# TouScruino-arm-ui2-v0.net
KiCad netlist of a schematic drawn in EAGLE
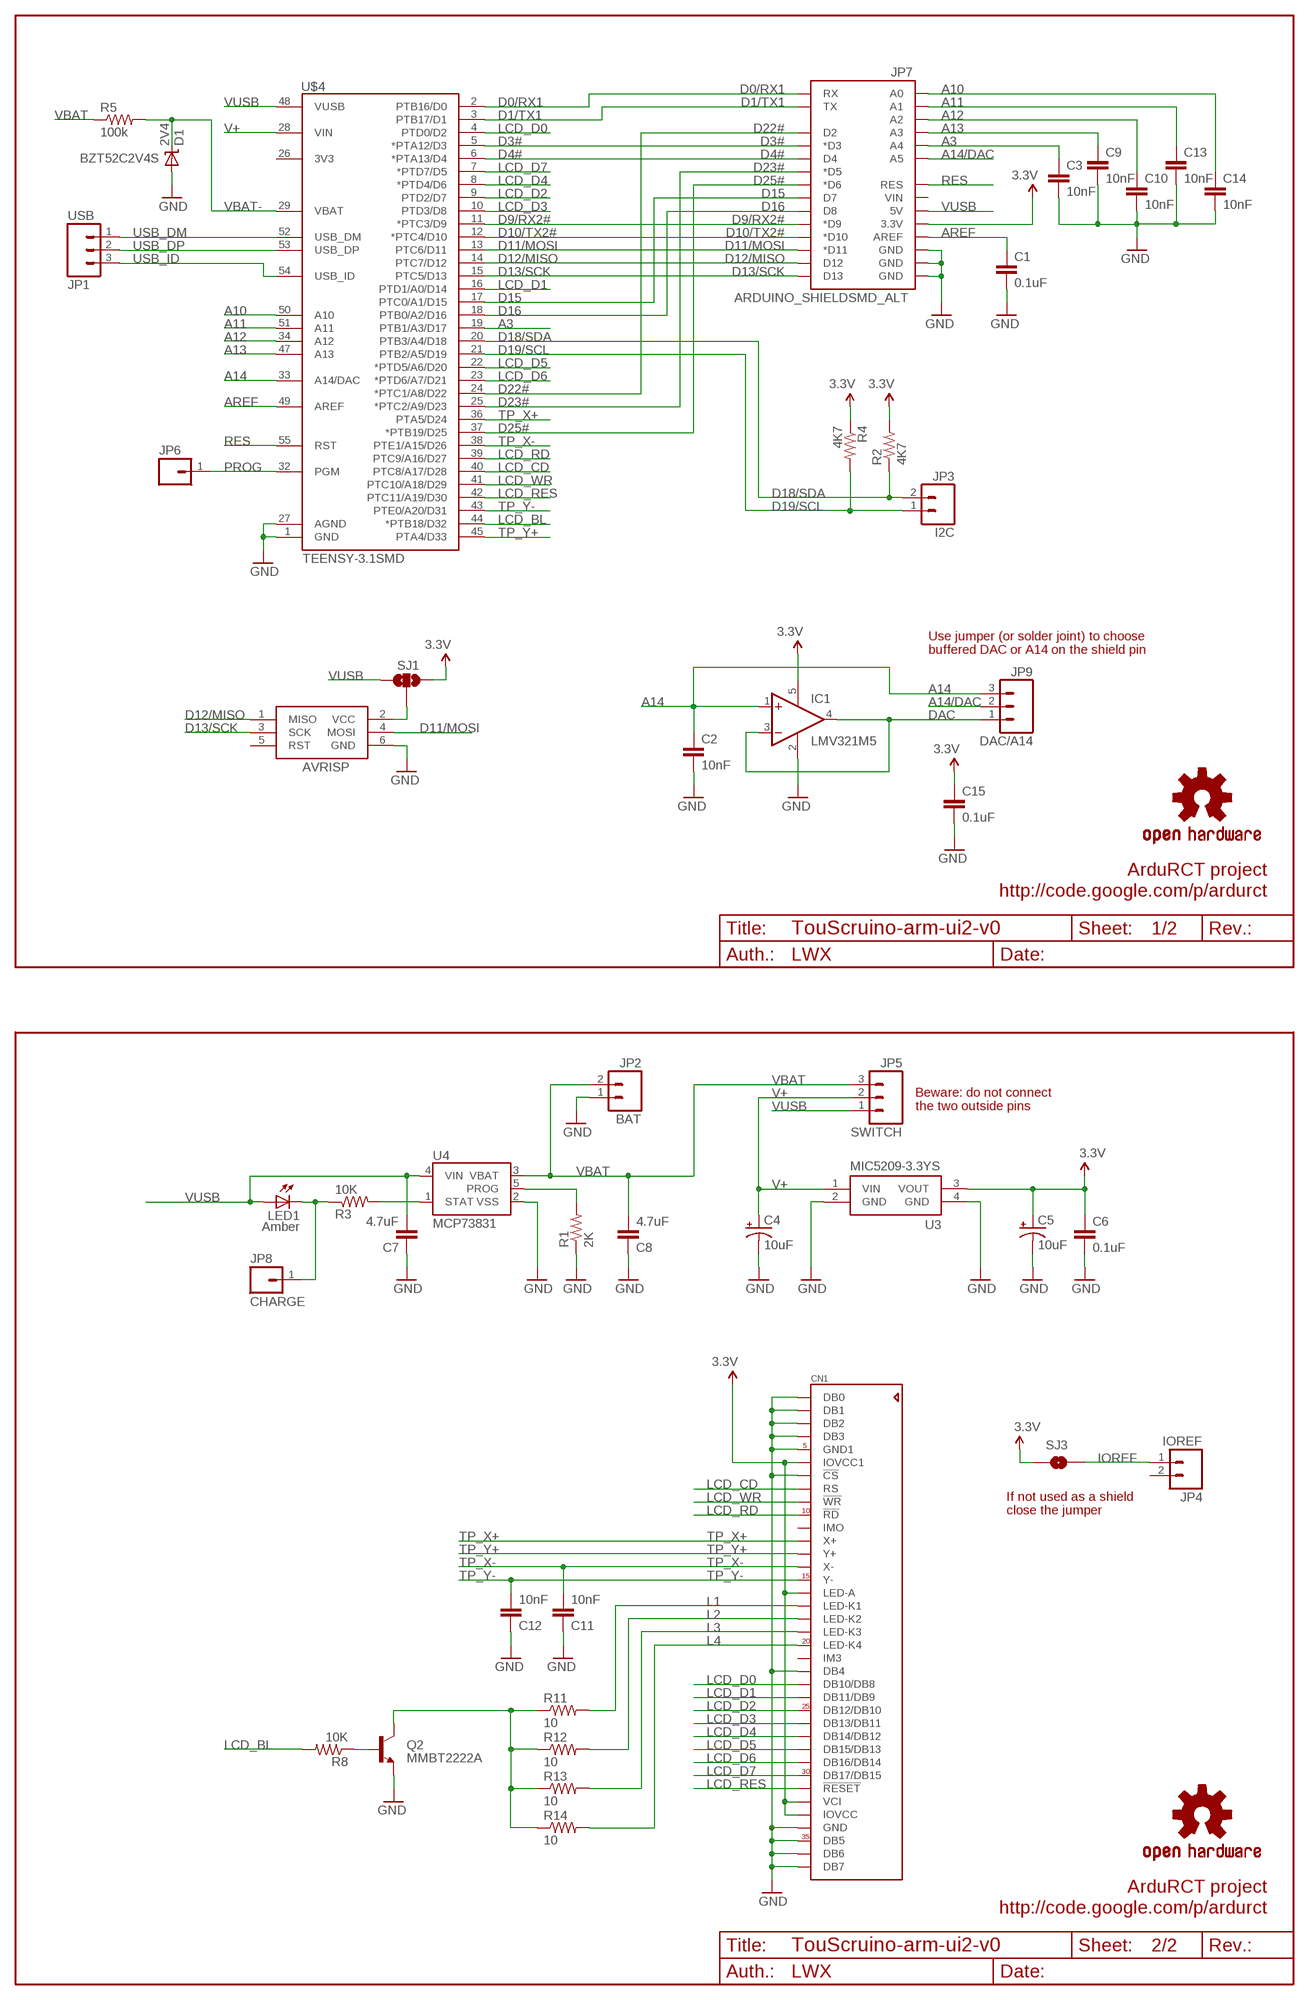
[diagram p0: schematic, sheet 1]

(export (version "E")
  (design (tool "Eeschema 10.0.6"))
  (components
    (comp (ref "AVRISP")
      (value "AVRISP")
      (footprint "eagle-import:2X3_SMD")
      (libsource (lib "eagle-import") (part "AVRISP"))
    )
    (comp (ref "C1")
      (value "0.1uF")
      (footprint "eagle-import:0805")
      (libsource (lib "eagle-import") (part "CAP0805"))
    )
    (comp (ref "C2")
      (value "10nF")
      (footprint "eagle-import:0805")
      (libsource (lib "eagle-import") (part "CAP0805"))
    )
    (comp (ref "C3")
      (value "10nF")
      (footprint "eagle-import:0805")
      (libsource (lib "eagle-import") (part "CAP0805"))
    )
    (comp (ref "C4")
      (value "10uF")
      (footprint "eagle-import:EIA3216")
      (libsource (lib "eagle-import") (part "CAP_POL1206"))
    )
    (comp (ref "C5")
      (value "10uF")
      (footprint "eagle-import:EIA3216")
      (libsource (lib "eagle-import") (part "CAP_POL1206"))
    )
    (comp (ref "C6")
      (value "0.1uF")
      (footprint "eagle-import:0805")
      (libsource (lib "eagle-import") (part "CAP0805"))
    )
    (comp (ref "C7")
      (value "4.7uF")
      (footprint "eagle-import:0805")
      (libsource (lib "eagle-import") (part "CAP0805"))
    )
    (comp (ref "C8")
      (value "4.7uF")
      (footprint "eagle-import:0805")
      (libsource (lib "eagle-import") (part "CAP0805"))
    )
    (comp (ref "C9")
      (value "10nF")
      (footprint "eagle-import:0805")
      (libsource (lib "eagle-import") (part "CAP0805"))
    )
    (comp (ref "C10")
      (value "10nF")
      (footprint "eagle-import:0805")
      (libsource (lib "eagle-import") (part "CAP0805"))
    )
    (comp (ref "C11")
      (value "10nF")
      (footprint "eagle-import:0805")
      (libsource (lib "eagle-import") (part "CAP0805"))
    )
    (comp (ref "C12")
      (value "10nF")
      (footprint "eagle-import:0805")
      (libsource (lib "eagle-import") (part "CAP0805"))
    )
    (comp (ref "C13")
      (value "10nF")
      (footprint "eagle-import:0805")
      (libsource (lib "eagle-import") (part "CAP0805"))
    )
    (comp (ref "C14")
      (value "10nF")
      (footprint "eagle-import:0805")
      (libsource (lib "eagle-import") (part "CAP0805"))
    )
    (comp (ref "C15")
      (value "0.1uF")
      (footprint "eagle-import:0805")
      (libsource (lib "eagle-import") (part "CAP0805"))
    )
    (comp (ref "CN1")
      (value "ILI9325_LCD1.0MM")
      (footprint "eagle-import:ILI9325_28INCH_TS")
      (libsource (lib "eagle-import") (part "ILI9325_LCD1.0MM"))
    )
    (comp (ref "D1")
      (value "2V4")
      (footprint "eagle-import:SOD-323")
      (libsource (lib "eagle-import") (part "DIODE-ZENER-BZT52"))
    )
    (comp (ref "IC1")
      (value "LMV321M5")
      (footprint "eagle-import:SOT23-5")
      (libsource (lib "eagle-import") (part "LMV321?M5"))
    )
    (comp (ref "JP1")
      (value "USB")
      (footprint "eagle-import:1X03_SMD_ALT")
      (libsource (lib "eagle-import") (part "M03SMD"))
    )
    (comp (ref "JP2")
      (value "BAT")
      (footprint "eagle-import:JST-2-SMD")
      (libsource (lib "eagle-import") (part "M02-JST-2MM-SMT"))
    )
    (comp (ref "JP3")
      (value "I2C")
      (footprint "eagle-import:1X02_SMD_ALT")
      (libsource (lib "eagle-import") (part "M02SMD_ALT"))
    )
    (comp (ref "JP4")
      (value "IOREF")
      (footprint "eagle-import:1X02_SMD_ALT")
      (libsource (lib "eagle-import") (part "M02SMD_ALT"))
    )
    (comp (ref "JP5")
      (value "SWITCH")
      (footprint "eagle-import:1X03_SMD_TH")
      (libsource (lib "eagle-import") (part "M03SMD_TH"))
    )
    (comp (ref "JP6")
      (value "M01SMD_TH")
      (footprint "eagle-import:1X01_SMD_TH")
      (libsource (lib "eagle-import") (part "M01SMD_TH"))
    )
    (comp (ref "JP7")
      (value "ARDUINO_SHIELDSMD_ALT")
      (footprint "eagle-import:ARDUINO_SHIELD_SMD_ALT")
      (libsource (lib "eagle-import") (part "ARDUINO_SHIELDSMD_ALT"))
    )
    (comp (ref "JP8")
      (value "CHARGE")
      (footprint "eagle-import:1X01_SMD")
      (libsource (lib "eagle-import") (part "M01SMD"))
    )
    (comp (ref "JP9")
      (value "DAC/A14")
      (footprint "eagle-import:1X03_SMD_SJ")
      (libsource (lib "eagle-import") (part "M03SMD_SJ"))
    )
    (comp (ref "LED1")
      (value "Amber")
      (footprint "eagle-import:LED")
      (libsource (lib "eagle-import") (part "LED"))
    )
    (comp (ref "Q2")
      (value "MMBT2222A")
      (footprint "eagle-import:SOT23-3")
      (libsource (lib "eagle-import") (part "TRANSISTOR_NPNSOT23-3"))
    )
    (comp (ref "R1")
      (value "2K")
      (footprint "eagle-import:0805")
      (libsource (lib "eagle-import") (part "RESISTOR0805-RES"))
    )
    (comp (ref "R2")
      (value "4K7")
      (footprint "eagle-import:0805")
      (libsource (lib "eagle-import") (part "RESISTOR0805-RES"))
    )
    (comp (ref "R3")
      (value "10K")
      (footprint "eagle-import:0805")
      (libsource (lib "eagle-import") (part "RESISTOR0805-RES"))
    )
    (comp (ref "R4")
      (value "4K7")
      (footprint "eagle-import:0805")
      (libsource (lib "eagle-import") (part "RESISTOR0805-RES"))
    )
    (comp (ref "R5")
      (value "100k")
      (footprint "eagle-import:0805")
      (libsource (lib "eagle-import") (part "RESISTOR0805-RES"))
    )
    (comp (ref "R8")
      (value "10K")
      (footprint "eagle-import:0805")
      (libsource (lib "eagle-import") (part "RESISTOR0805-RES"))
    )
    (comp (ref "R11")
      (value "10")
      (footprint "eagle-import:0805")
      (libsource (lib "eagle-import") (part "RESISTOR0805-RES"))
    )
    (comp (ref "R12")
      (value "10")
      (footprint "eagle-import:0805")
      (libsource (lib "eagle-import") (part "RESISTOR0805-RES"))
    )
    (comp (ref "R13")
      (value "10")
      (footprint "eagle-import:0805")
      (libsource (lib "eagle-import") (part "RESISTOR0805-RES"))
    )
    (comp (ref "R14")
      (value "10")
      (footprint "eagle-import:0805")
      (libsource (lib "eagle-import") (part "RESISTOR0805-RES"))
    )
    (comp (ref "SJ1")
      (value "SJ_2WAYS")
      (footprint "eagle-import:SJ_2WAYS")
      (libsource (lib "eagle-import") (part "SJ_2WAYS"))
    )
    (comp (ref "SJ3")
      (value "SOLDERJUMPERNO")
      (footprint "eagle-import:SJ_2S-NO")
      (libsource (lib "eagle-import") (part "SOLDERJUMPERNO"))
    )
    (comp (ref "U$3")
      (value "OSHW-LOGOM")
      (footprint "eagle-import:OSHW-LOGO-M")
      (libsource (lib "eagle-import") (part "OSHW-LOGOM"))
    )
    (comp (ref "U$4")
      (value "TEENSY-3.1SMD")
      (footprint "eagle-import:TEENSY-3.1_HSMD")
      (libsource (lib "eagle-import") (part "TEENSY-3.1SMD"))
    )
    (comp (ref "U$5")
      (value "OSHW-LOGOM")
      (footprint "eagle-import:OSHW-LOGO-M")
      (libsource (lib "eagle-import") (part "OSHW-LOGOM"))
    )
    (comp (ref "U3")
      (value "MIC5209-3.3YS")
      (footprint "eagle-import:SOT223")
      (libsource (lib "eagle-import") (part "MIC5209"))
    )
    (comp (ref "U4")
      (value "MCP73831")
      (footprint "eagle-import:SOT23-5")
      (libsource (lib "eagle-import") (part "MCP73831"))
    )
  )
  (nets
    (net (code "1") (name "/A3") (class "Default")
      (node (ref "C3") (pin "1") (pinfunction "1_1") (pintype "passive"))
      (node (ref "JP7") (pin "A4") (pinfunction "A4_A4") (pintype "bidirectional"))
      (node (ref "U$4") (pin "19") (pinfunction "PTB1/A3/D17_19") (pintype "bidirectional"))
    )
    (net (code "2") (name "/A10") (class "Default")
      (node (ref "C14") (pin "1") (pinfunction "1_1") (pintype "passive"))
      (node (ref "JP7") (pin "A0") (pinfunction "A0_A0") (pintype "bidirectional"))
      (node (ref "U$4") (pin "50") (pinfunction "A10_50") (pintype "bidirectional"))
    )
    (net (code "3") (name "/A11") (class "Default")
      (node (ref "C13") (pin "1") (pinfunction "1_1") (pintype "passive"))
      (node (ref "JP7") (pin "A1") (pinfunction "A1_A1") (pintype "bidirectional"))
      (node (ref "U$4") (pin "51") (pinfunction "A11_51") (pintype "bidirectional"))
    )
    (net (code "4") (name "/A12") (class "Default")
      (node (ref "C10") (pin "1") (pinfunction "1_1") (pintype "passive"))
      (node (ref "JP7") (pin "A2") (pinfunction "A2_A2") (pintype "bidirectional"))
      (node (ref "U$4") (pin "34") (pinfunction "A12_34") (pintype "bidirectional"))
    )
    (net (code "5") (name "/A13") (class "Default")
      (node (ref "C9") (pin "1") (pinfunction "1_1") (pintype "passive"))
      (node (ref "JP7") (pin "A3") (pinfunction "A3_A3") (pintype "bidirectional"))
      (node (ref "U$4") (pin "47") (pinfunction "A13_47") (pintype "bidirectional"))
    )
    (net (code "6") (name "/A14") (class "Default")
      (node (ref "C2") (pin "1") (pinfunction "1_1") (pintype "passive"))
      (node (ref "IC1") (pin "1") (pinfunction "+IN_1") (pintype "input"))
      (node (ref "JP9") (pin "3") (pinfunction "3_3") (pintype "passive"))
      (node (ref "U$4") (pin "33") (pinfunction "A14/DAC_33") (pintype "bidirectional"))
    )
    (net (code "7") (name "/A14{slash}DAC") (class "Default")
      (node (ref "JP7") (pin "A5") (pinfunction "A5_A5") (pintype "bidirectional"))
      (node (ref "JP9") (pin "2") (pinfunction "2_2") (pintype "passive"))
    )
    (net (code "8") (name "/AREF") (class "Default")
      (node (ref "C1") (pin "1") (pinfunction "1_1") (pintype "passive"))
      (node (ref "JP7") (pin "AREF") (pinfunction "AREF_AREF") (pintype "bidirectional"))
      (node (ref "U$4") (pin "49") (pinfunction "AREF_49") (pintype "bidirectional"))
    )
    (net (code "9") (name "/D0{slash}RX1") (class "Default")
      (node (ref "JP7") (pin "RX") (pinfunction "RX_RX") (pintype "bidirectional"))
      (node (ref "U$4") (pin "2") (pinfunction "PTB16/D0_2") (pintype "bidirectional"))
    )
    (net (code "10") (name "/D1{slash}TX1") (class "Default")
      (node (ref "JP7") (pin "TX") (pinfunction "TX_TX") (pintype "bidirectional"))
      (node (ref "U$4") (pin "3") (pinfunction "PTB17/D1_3") (pintype "bidirectional"))
    )
    (net (code "11") (name "/D3#") (class "Default")
      (node (ref "JP7") (pin "D3") (pinfunction "*D3_D3") (pintype "bidirectional"))
      (node (ref "U$4") (pin "5") (pinfunction "*PTA12/D3_5") (pintype "bidirectional"))
    )
    (net (code "12") (name "/D4#") (class "Default")
      (node (ref "JP7") (pin "D4") (pinfunction "D4_D4") (pintype "bidirectional"))
      (node (ref "U$4") (pin "6") (pinfunction "*PTA13/D4_6") (pintype "bidirectional"))
    )
    (net (code "13") (name "/D9{slash}RX2#") (class "Default")
      (node (ref "JP7") (pin "D9") (pinfunction "*D9_D9") (pintype "bidirectional"))
      (node (ref "U$4") (pin "11") (pinfunction "*PTC3/D9_11") (pintype "bidirectional"))
    )
    (net (code "14") (name "/D10{slash}TX2#") (class "Default")
      (node (ref "JP7") (pin "D10") (pinfunction "*D10_D10") (pintype "bidirectional"))
      (node (ref "U$4") (pin "12") (pinfunction "*PTC4/D10_12") (pintype "bidirectional"))
    )
    (net (code "15") (name "/D11{slash}MOSI") (class "Default")
      (node (ref "AVRISP") (pin "4") (pinfunction "MOSI_4") (pintype "output"))
      (node (ref "JP7") (pin "D11") (pinfunction "*D11_D11") (pintype "bidirectional"))
      (node (ref "U$4") (pin "13") (pinfunction "PTC6/D11_13") (pintype "bidirectional"))
    )
    (net (code "16") (name "/D12{slash}MISO") (class "Default")
      (node (ref "AVRISP") (pin "1") (pinfunction "MISO_1") (pintype "input"))
      (node (ref "JP7") (pin "D12") (pinfunction "D12_D12") (pintype "bidirectional"))
      (node (ref "U$4") (pin "14") (pinfunction "PTC7/D12_14") (pintype "bidirectional"))
    )
    (net (code "17") (name "/D13{slash}SCK") (class "Default")
      (node (ref "AVRISP") (pin "3") (pinfunction "SCK_3") (pintype "output"))
      (node (ref "JP7") (pin "D13") (pinfunction "D13_D13") (pintype "bidirectional"))
      (node (ref "U$4") (pin "15") (pinfunction "PTC5/D13_15") (pintype "bidirectional"))
    )
    (net (code "18") (name "/D15") (class "Default")
      (node (ref "JP7") (pin "D7") (pinfunction "D7_D7") (pintype "bidirectional"))
      (node (ref "U$4") (pin "17") (pinfunction "PTC0/A1/D15_17") (pintype "bidirectional"))
    )
    (net (code "19") (name "/D16") (class "Default")
      (node (ref "JP7") (pin "D8") (pinfunction "D8_D8") (pintype "bidirectional"))
      (node (ref "U$4") (pin "18") (pinfunction "PTB0/A2/D16_18") (pintype "bidirectional"))
    )
    (net (code "20") (name "/D18{slash}SDA") (class "Default")
      (node (ref "JP3") (pin "2") (pinfunction "2_2") (pintype "passive"))
      (node (ref "R2") (pin "1") (pinfunction "1_1") (pintype "passive"))
      (node (ref "U$4") (pin "20") (pinfunction "PTB3/A4/D18_20") (pintype "bidirectional"))
    )
    (net (code "21") (name "/D19{slash}SCL") (class "Default")
      (node (ref "JP3") (pin "1") (pinfunction "1_1") (pintype "passive"))
      (node (ref "R4") (pin "2") (pinfunction "2_2") (pintype "passive"))
      (node (ref "U$4") (pin "21") (pinfunction "PTB2/A5/D19_21") (pintype "bidirectional"))
    )
    (net (code "22") (name "/D22#") (class "Default")
      (node (ref "JP7") (pin "D2") (pinfunction "D2_D2") (pintype "bidirectional"))
      (node (ref "U$4") (pin "24") (pinfunction "*PTC1/A8/D22_24") (pintype "bidirectional"))
    )
    (net (code "23") (name "/D23#") (class "Default")
      (node (ref "JP7") (pin "D5") (pinfunction "*D5_D5") (pintype "bidirectional"))
      (node (ref "U$4") (pin "25") (pinfunction "*PTC2/A9/D23_25") (pintype "bidirectional"))
    )
    (net (code "24") (name "/D25#") (class "Default")
      (node (ref "JP7") (pin "D6") (pinfunction "*D6_D6") (pintype "bidirectional"))
      (node (ref "U$4") (pin "37") (pinfunction "*PTB19/D25_37") (pintype "bidirectional"))
    )
    (net (code "25") (name "/DAC") (class "Default")
      (node (ref "IC1") (pin "3") (pinfunction "-IN_3") (pintype "input"))
      (node (ref "IC1") (pin "4") (pinfunction "OUT_4") (pintype "output"))
      (node (ref "JP9") (pin "1") (pinfunction "1_1") (pintype "passive"))
    )
    (net (code "26") (name "/IOREF") (class "Default")
      (node (ref "JP4") (pin "1") (pinfunction "1_1") (pintype "passive"))
      (node (ref "SJ3") (pin "2") (pinfunction "2_2") (pintype "passive"))
    )
    (net (code "27") (name "/L1") (class "Default")
      (node (ref "CN1") (pin "17") (pinfunction "LED-K1_17") (pintype "passive"))
      (node (ref "R11") (pin "2") (pinfunction "2_2") (pintype "passive"))
    )
    (net (code "28") (name "/L2") (class "Default")
      (node (ref "CN1") (pin "18") (pinfunction "LED-K2_18") (pintype "passive"))
      (node (ref "R12") (pin "2") (pinfunction "2_2") (pintype "passive"))
    )
    (net (code "29") (name "/L3") (class "Default")
      (node (ref "CN1") (pin "19") (pinfunction "LED-K3_19") (pintype "passive"))
      (node (ref "R13") (pin "2") (pinfunction "2_2") (pintype "passive"))
    )
    (net (code "30") (name "/L4") (class "Default")
      (node (ref "CN1") (pin "20") (pinfunction "LED-K4_20") (pintype "passive"))
      (node (ref "R14") (pin "2") (pinfunction "2_2") (pintype "passive"))
    )
    (net (code "31") (name "/LCD_BL") (class "Default")
      (node (ref "R8") (pin "2") (pinfunction "2_2") (pintype "passive"))
      (node (ref "U$4") (pin "44") (pinfunction "*PTB18/D32_44") (pintype "bidirectional"))
    )
    (net (code "32") (name "/LCD_CD") (class "Default")
      (node (ref "CN1") (pin "8") (pinfunction "RS_8") (pintype "passive"))
      (node (ref "U$4") (pin "40") (pinfunction "PTC8/A17/D28_40") (pintype "bidirectional"))
    )
    (net (code "33") (name "/LCD_D0") (class "Default")
      (node (ref "CN1") (pin "23") (pinfunction "DB10/DB8_23") (pintype "passive"))
      (node (ref "U$4") (pin "4") (pinfunction "PTD0/D2_4") (pintype "bidirectional"))
    )
    (net (code "34") (name "/LCD_D1") (class "Default")
      (node (ref "CN1") (pin "24") (pinfunction "DB11/DB9_24") (pintype "passive"))
      (node (ref "U$4") (pin "16") (pinfunction "PTD1/A0/D14_16") (pintype "bidirectional"))
    )
    (net (code "35") (name "/LCD_D2") (class "Default")
      (node (ref "CN1") (pin "25") (pinfunction "DB12/DB10_25") (pintype "passive"))
      (node (ref "U$4") (pin "9") (pinfunction "PTD2/D7_9") (pintype "bidirectional"))
    )
    (net (code "36") (name "/LCD_D3") (class "Default")
      (node (ref "CN1") (pin "26") (pinfunction "DB13/DB11_26") (pintype "passive"))
      (node (ref "U$4") (pin "10") (pinfunction "PTD3/D8_10") (pintype "bidirectional"))
    )
    (net (code "37") (name "/LCD_D4") (class "Default")
      (node (ref "CN1") (pin "27") (pinfunction "DB14/DB12_27") (pintype "passive"))
      (node (ref "U$4") (pin "8") (pinfunction "*PTD4/D6_8") (pintype "bidirectional"))
    )
    (net (code "38") (name "/LCD_D5") (class "Default")
      (node (ref "CN1") (pin "28") (pinfunction "DB15/DB13_28") (pintype "passive"))
      (node (ref "U$4") (pin "22") (pinfunction "*PTD5/A6/D20_22") (pintype "bidirectional"))
    )
    (net (code "39") (name "/LCD_D6") (class "Default")
      (node (ref "CN1") (pin "29") (pinfunction "DB16/DB14_29") (pintype "passive"))
      (node (ref "U$4") (pin "23") (pinfunction "*PTD6/A7/D21_23") (pintype "bidirectional"))
    )
    (net (code "40") (name "/LCD_D7") (class "Default")
      (node (ref "CN1") (pin "30") (pinfunction "DB17/DB15_30") (pintype "passive"))
      (node (ref "U$4") (pin "7") (pinfunction "*PTD7/D5_7") (pintype "bidirectional"))
    )
    (net (code "41") (name "/LCD_RD") (class "Default")
      (node (ref "CN1") (pin "10") (pinfunction "~{RD}_10") (pintype "passive"))
      (node (ref "U$4") (pin "39") (pinfunction "PTC9/A16/D27_39") (pintype "bidirectional"))
    )
    (net (code "42") (name "/LCD_RES") (class "Default")
      (node (ref "CN1") (pin "31") (pinfunction "~{RESET}_31") (pintype "passive"))
      (node (ref "U$4") (pin "42") (pinfunction "PTC11/A19/D30_42") (pintype "bidirectional"))
    )
    (net (code "43") (name "/LCD_WR") (class "Default")
      (node (ref "CN1") (pin "9") (pinfunction "~{WR}_9") (pintype "passive"))
      (node (ref "U$4") (pin "41") (pinfunction "PTC10/A18/D29_41") (pintype "bidirectional"))
    )
    (net (code "44") (name "/PROG") (class "Default")
      (node (ref "JP6") (pin "1") (pinfunction "1_1") (pintype "passive"))
      (node (ref "U$4") (pin "32") (pinfunction "PGM_32") (pintype "bidirectional"))
    )
    (net (code "45") (name "/RES") (class "Default")
      (node (ref "JP7") (pin "RES") (pinfunction "RES_RES") (pintype "bidirectional"))
      (node (ref "U$4") (pin "55") (pinfunction "RST_55") (pintype "bidirectional"))
    )
    (net (code "46") (name "/TP_X+") (class "Default")
      (node (ref "CN1") (pin "12") (pinfunction "X+_12") (pintype "passive"))
      (node (ref "U$4") (pin "36") (pinfunction "PTA5/D24_36") (pintype "bidirectional"))
    )
    (net (code "47") (name "/TP_X-") (class "Default")
      (node (ref "C11") (pin "2") (pinfunction "2_2") (pintype "passive"))
      (node (ref "CN1") (pin "14") (pinfunction "X-_14") (pintype "passive"))
      (node (ref "U$4") (pin "38") (pinfunction "PTE1/A15/D26_38") (pintype "bidirectional"))
    )
    (net (code "48") (name "/TP_Y+") (class "Default")
      (node (ref "CN1") (pin "13") (pinfunction "Y+_13") (pintype "passive"))
      (node (ref "U$4") (pin "45") (pinfunction "PTA4/D33_45") (pintype "bidirectional"))
    )
    (net (code "49") (name "/TP_Y-") (class "Default")
      (node (ref "C12") (pin "2") (pinfunction "2_2") (pintype "passive"))
      (node (ref "CN1") (pin "15") (pinfunction "Y-_15") (pintype "passive"))
      (node (ref "U$4") (pin "43") (pinfunction "PTE0/A20/D31_43") (pintype "bidirectional"))
    )
    (net (code "50") (name "/USB_DM") (class "Default")
      (node (ref "JP1") (pin "1") (pinfunction "1_1") (pintype "passive"))
      (node (ref "U$4") (pin "52") (pinfunction "USB_DM_52") (pintype "bidirectional"))
    )
    (net (code "51") (name "/USB_DP") (class "Default")
      (node (ref "JP1") (pin "2") (pinfunction "2_2") (pintype "passive"))
      (node (ref "U$4") (pin "53") (pinfunction "USB_DP_53") (pintype "bidirectional"))
    )
    (net (code "52") (name "/USB_ID") (class "Default")
      (node (ref "JP1") (pin "3") (pinfunction "3_3") (pintype "passive"))
      (node (ref "U$4") (pin "54") (pinfunction "USB_ID_54") (pintype "bidirectional"))
    )
    (net (code "53") (name "/V+") (class "Default")
      (node (ref "C4") (pin "A") (pinfunction "+_A") (pintype "passive"))
      (node (ref "JP5") (pin "2") (pinfunction "2_2") (pintype "passive"))
      (node (ref "U$4") (pin "28") (pinfunction "VIN_28") (pintype "bidirectional"))
      (node (ref "U3") (pin "1") (pinfunction "VIN_1") (pintype "bidirectional"))
    )
    (net (code "54") (name "/VBAT") (class "Default")
      (node (ref "C8") (pin "2") (pinfunction "2_2") (pintype "passive"))
      (node (ref "JP2") (pin "2") (pinfunction "2_2") (pintype "passive"))
      (node (ref "JP5") (pin "3") (pinfunction "3_3") (pintype "passive"))
      (node (ref "R5") (pin "1") (pinfunction "1_1") (pintype "passive"))
      (node (ref "U4") (pin "3") (pinfunction "VBAT_3") (pintype "power_in"))
    )
    (net (code "55") (name "/VBAT-") (class "Default")
      (node (ref "D1") (pin "1") (pinfunction "C_1") (pintype "passive"))
      (node (ref "R5") (pin "2") (pinfunction "2_2") (pintype "passive"))
      (node (ref "U$4") (pin "29") (pinfunction "VBAT_29") (pintype "bidirectional"))
    )
    (net (code "56") (name "/VUSB") (class "Default")
      (node (ref "C7") (pin "2") (pinfunction "2_2") (pintype "passive"))
      (node (ref "JP5") (pin "1") (pinfunction "1_1") (pintype "passive"))
      (node (ref "JP7") (pin "5V") (pinfunction "5V_5V") (pintype "bidirectional"))
      (node (ref "LED1") (pin "A1") (pinfunction "A_A1") (pintype "passive"))
      (node (ref "SJ1") (pin "1") (pinfunction "1_1") (pintype "passive"))
      (node (ref "U$4") (pin "48") (pinfunction "VUSB_48") (pintype "bidirectional"))
      (node (ref "U4") (pin "4") (pinfunction "VIN_4") (pintype "power_in"))
    )
    (net (code "57") (name "3.3V") (class "Default")
      (node (ref "C15") (pin "1") (pinfunction "1_1") (pintype "passive"))
      (node (ref "C5") (pin "A") (pinfunction "+_A") (pintype "passive"))
      (node (ref "C6") (pin "1") (pinfunction "1_1") (pintype "passive"))
      (node (ref "CN1") (pin "16") (pinfunction "LED-A_16") (pintype "passive"))
      (node (ref "CN1") (pin "32") (pinfunction "VCI_32") (pintype "power_in"))
      (node (ref "CN1") (pin "33") (pinfunction "IOVCC_33") (pintype "power_in"))
      (node (ref "CN1") (pin "6") (pinfunction "IOVCC1_6") (pintype "power_in"))
      (node (ref "IC1") (pin "5") (pinfunction "V+_5") (pintype "power_in"))
      (node (ref "JP7") (pin "3.3V") (pinfunction "3.3V_3.3V") (pintype "bidirectional"))
      (node (ref "R2") (pin "2") (pinfunction "2_2") (pintype "passive"))
      (node (ref "R4") (pin "1") (pinfunction "1_1") (pintype "passive"))
      (node (ref "SJ1") (pin "3") (pinfunction "3_3") (pintype "passive"))
      (node (ref "SJ3") (pin "1") (pinfunction "1_1") (pintype "passive"))
      (node (ref "U3") (pin "3") (pinfunction "VOUT_3") (pintype "bidirectional"))
    )
    (net (code "58") (name "GND") (class "Default")
      (node (ref "AVRISP") (pin "6") (pinfunction "GND_6") (pintype "power_in"))
      (node (ref "C1") (pin "2") (pinfunction "2_2") (pintype "passive"))
      (node (ref "C10") (pin "2") (pinfunction "2_2") (pintype "passive"))
      (node (ref "C11") (pin "1") (pinfunction "1_1") (pintype "passive"))
      (node (ref "C12") (pin "1") (pinfunction "1_1") (pintype "passive"))
      (node (ref "C13") (pin "2") (pinfunction "2_2") (pintype "passive"))
      (node (ref "C14") (pin "2") (pinfunction "2_2") (pintype "passive"))
      (node (ref "C15") (pin "2") (pinfunction "2_2") (pintype "passive"))
      (node (ref "C2") (pin "2") (pinfunction "2_2") (pintype "passive"))
      (node (ref "C3") (pin "2") (pinfunction "2_2") (pintype "passive"))
      (node (ref "C4") (pin "C") (pinfunction "-_C") (pintype "passive"))
      (node (ref "C5") (pin "C") (pinfunction "-_C") (pintype "passive"))
      (node (ref "C6") (pin "2") (pinfunction "2_2") (pintype "passive"))
      (node (ref "C7") (pin "1") (pinfunction "1_1") (pintype "passive"))
      (node (ref "C8") (pin "1") (pinfunction "1_1") (pintype "passive"))
      (node (ref "C9") (pin "2") (pinfunction "2_2") (pintype "passive"))
      (node (ref "CN1") (pin "1") (pinfunction "DB0_1") (pintype "passive"))
      (node (ref "CN1") (pin "2") (pinfunction "DB1_2") (pintype "passive"))
      (node (ref "CN1") (pin "22") (pinfunction "DB4_22") (pintype "passive"))
      (node (ref "CN1") (pin "3") (pinfunction "DB2_3") (pintype "passive"))
      (node (ref "CN1") (pin "34") (pinfunction "GND_34") (pintype "power_in"))
      (node (ref "CN1") (pin "35") (pinfunction "DB5_35") (pintype "passive"))
      (node (ref "CN1") (pin "36") (pinfunction "DB6_36") (pintype "passive"))
      (node (ref "CN1") (pin "37") (pinfunction "DB7_37") (pintype "passive"))
      (node (ref "CN1") (pin "4") (pinfunction "DB3_4") (pintype "passive"))
      (node (ref "CN1") (pin "5") (pinfunction "GND1_5") (pintype "power_in"))
      (node (ref "CN1") (pin "7") (pinfunction "~{CS}_7") (pintype "passive"))
      (node (ref "D1") (pin "2") (pinfunction "A_2") (pintype "passive"))
      (node (ref "IC1") (pin "2") (pinfunction "V-_2") (pintype "power_in"))
      (node (ref "JP2") (pin "1") (pinfunction "1_1") (pintype "passive"))
      (node (ref "JP7") (pin "GND@0") (pinfunction "GND_GND@0") (pintype "bidirectional"))
      (node (ref "JP7") (pin "GND@1") (pinfunction "GND_GND@1") (pintype "bidirectional"))
      (node (ref "JP7") (pin "GND@2") (pinfunction "GND_GND@2") (pintype "bidirectional"))
      (node (ref "Q2") (pin "2") (pinfunction "E_2") (pintype "passive"))
      (node (ref "R1") (pin "1") (pinfunction "1_1") (pintype "passive"))
      (node (ref "U$4") (pin "1") (pinfunction "GND_1") (pintype "bidirectional"))
      (node (ref "U$4") (pin "27") (pinfunction "AGND_27") (pintype "bidirectional"))
      (node (ref "U3") (pin "2") (pinfunction "GND_2") (pintype "bidirectional"))
      (node (ref "U3") (pin "4") (pinfunction "GND_4") (pintype "bidirectional"))
      (node (ref "U4") (pin "2") (pinfunction "VSS_2") (pintype "power_in"))
    )
    (net (code "59") (name "Net-(AVRISP-VCC)") (class "Default")
      (node (ref "AVRISP") (pin "2") (pinfunction "VCC_2") (pintype "power_in"))
      (node (ref "SJ1") (pin "2") (pinfunction "2_2") (pintype "passive"))
    )
    (net (code "60") (name "Net-(LED1-C)") (class "Default")
      (node (ref "JP8") (pin "1") (pinfunction "1_1") (pintype "passive"))
      (node (ref "LED1") (pin "C1") (pinfunction "C_C1") (pintype "passive"))
      (node (ref "R3") (pin "1") (pinfunction "1_1") (pintype "passive"))
    )
    (net (code "61") (name "Net-(Q2-B)") (class "Default")
      (node (ref "Q2") (pin "1") (pinfunction "B_1") (pintype "passive"))
      (node (ref "R8") (pin "1") (pinfunction "1_1") (pintype "passive"))
    )
    (net (code "62") (name "Net-(Q2-C)") (class "Default")
      (node (ref "Q2") (pin "3") (pinfunction "C_3") (pintype "passive"))
      (node (ref "R11") (pin "1") (pinfunction "1_1") (pintype "passive"))
      (node (ref "R12") (pin "1") (pinfunction "1_1") (pintype "passive"))
      (node (ref "R13") (pin "1") (pinfunction "1_1") (pintype "passive"))
      (node (ref "R14") (pin "1") (pinfunction "1_1") (pintype "passive"))
    )
    (net (code "63") (name "Net-(U4-PROG)") (class "Default")
      (node (ref "R1") (pin "2") (pinfunction "2_2") (pintype "passive"))
      (node (ref "U4") (pin "5") (pinfunction "PROG_5") (pintype "input"))
    )
    (net (code "64") (name "Net-(U4-STAT)") (class "Default")
      (node (ref "R3") (pin "2") (pinfunction "2_2") (pintype "passive"))
      (node (ref "U4") (pin "1") (pinfunction "STAT_1") (pintype "output"))
    )
    (net (code "65") (name "unconnected-(AVRISP-RST-Pad5)") (class "Default")
      (node (ref "AVRISP") (pin "5") (pinfunction "RST_5") (pintype "output"))
    )
    (net (code "66") (name "unconnected-(CN1-IM3-Pad21)") (class "Default")
      (node (ref "CN1") (pin "21") (pinfunction "IM3_21") (pintype "passive"))
    )
    (net (code "67") (name "unconnected-(CN1-IMO-Pad11)") (class "Default")
      (node (ref "CN1") (pin "11") (pinfunction "IMO_11") (pintype "passive"))
    )
    (net (code "68") (name "unconnected-(JP4-Pad2)") (class "Default")
      (node (ref "JP4") (pin "2") (pinfunction "2_2") (pintype "passive"))
    )
    (net (code "69") (name "unconnected-(JP7-PadVIN)") (class "Default")
      (node (ref "JP7") (pin "VIN") (pinfunction "VIN_VIN") (pintype "bidirectional"))
    )
    (net (code "70") (name "unconnected-(U$4-3V3-Pad26)") (class "Default")
      (node (ref "U$4") (pin "26") (pinfunction "3V3_26") (pintype "bidirectional"))
    )
  )
)
